# lan8742_daughterboard_EF.net
KiCad netlist of a schematic drawn in Altium Designer
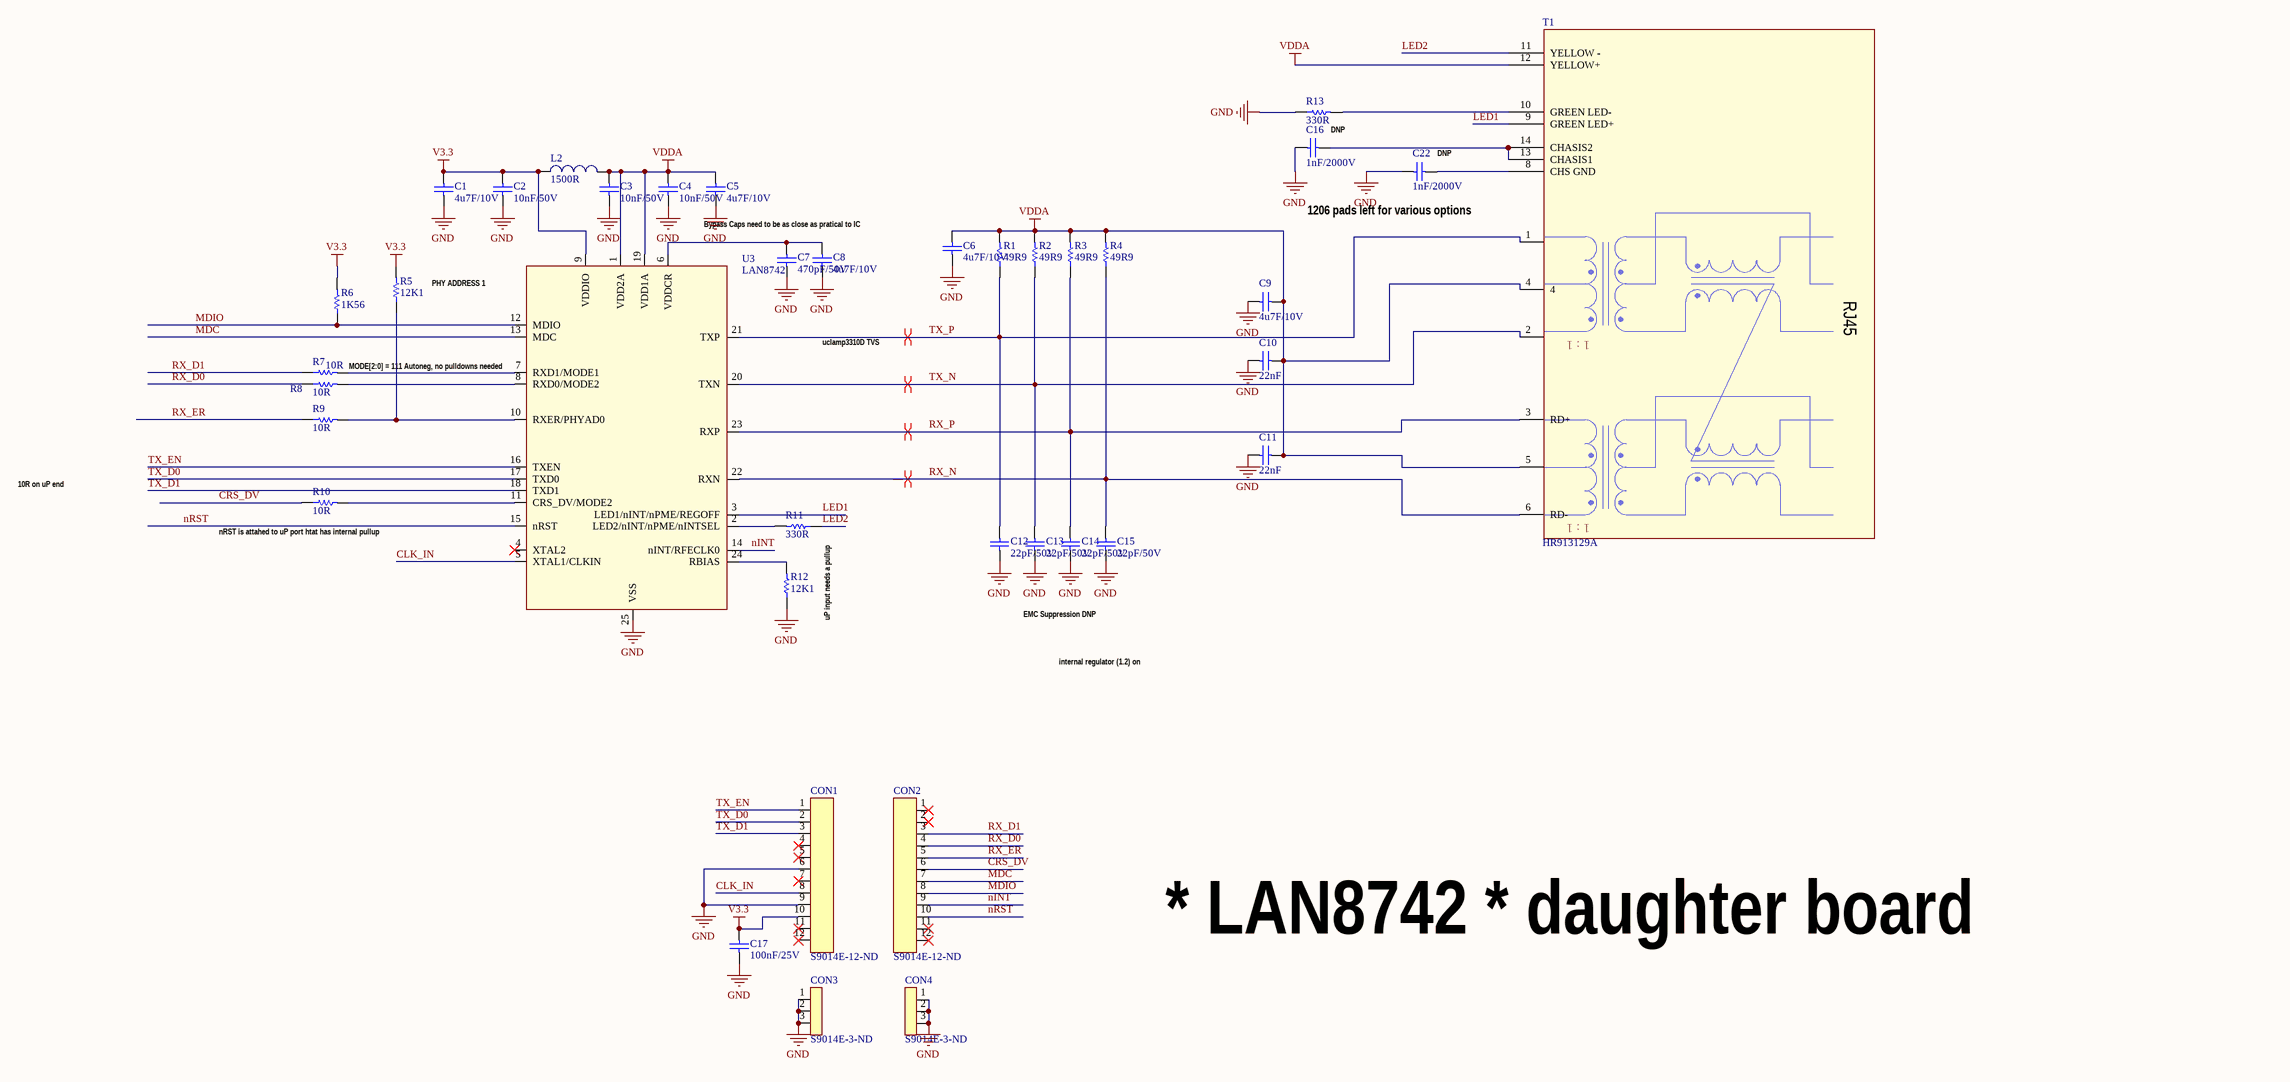
[diagram p0: lan8742_daughterboard_EF.SchDoc]

(export (version "E")
  (design (tool "Eeschema 10.0.6"))
  (components
    (comp (ref "C1")
      (value "CAP")
      (footprint "CAP_0603")
      (fields (field (name "PART NUMBER") "CAP_4u7F/10V_0603") (field (name "PART_VALUE") "4u7F/10V"))
      (libsource (lib "stellalib") (part "CAP"))
    )
    (comp (ref "C2")
      (value "CAP")
      (footprint "CAP_0603")
      (fields (field (name "PART NUMBER") "CAP_10nF/50V_0603") (field (name "PART_VALUE") "10nF/50V"))
      (libsource (lib "stellalib") (part "CAP"))
    )
    (comp (ref "C3")
      (value "CAP")
      (footprint "CAP_0603")
      (fields (field (name "PART NUMBER") "CAP_10nF/50V_0603") (field (name "PART_VALUE") "10nF/50V"))
      (libsource (lib "stellalib") (part "CAP"))
    )
    (comp (ref "C4")
      (value "CAP")
      (footprint "CAP_0603")
      (fields (field (name "PART NUMBER") "CAP_10nF/50V_0603") (field (name "PART_VALUE") "10nF/50V"))
      (libsource (lib "stellalib") (part "CAP"))
    )
    (comp (ref "C5")
      (value "CAP")
      (footprint "CAP_0603")
      (fields (field (name "PART NUMBER") "CAP_4u7F/10V_0603") (field (name "PART_VALUE") "4u7F/10V"))
      (libsource (lib "stellalib") (part "CAP"))
    )
    (comp (ref "C6")
      (value "CAP")
      (footprint "CAP_0603")
      (fields (field (name "PART NUMBER") "CAP_4u7F/10V_0603") (field (name "PART_VALUE") "4u7F/10V"))
      (libsource (lib "stellalib") (part "CAP"))
    )
    (comp (ref "C7")
      (value "CAP")
      (footprint "CAP_0603")
      (description "470pF Ceramic")
      (fields (field (name "PART NUMBER") "CAP_470pF/50V_0603") (field (name "PART_VALUE") "470pF/50V"))
      (libsource (lib "stellalib") (part "CAP"))
    )
    (comp (ref "C8")
      (value "CAP")
      (footprint "CAP_0603")
      (fields (field (name "PART NUMBER") "CAP_4u7F/10V_0603") (field (name "PART_VALUE") "4u7F/10V"))
      (libsource (lib "stellalib") (part "CAP"))
    )
    (comp (ref "C9")
      (value "CAP")
      (footprint "CAP_0603")
      (fields (field (name "PART NUMBER") "CAP_4u7F/10V_0603") (field (name "PART_VALUE") "4u7F/10V"))
      (libsource (lib "stellalib") (part "CAP"))
    )
    (comp (ref "C10")
      (value "CAP")
      (footprint "CAP_0603")
      (fields (field (name "PART NUMBER") "CAP_22nF/50V_0603") (field (name "PART_VALUE") "22nF"))
      (libsource (lib "stellalib") (part "CAP"))
    )
    (comp (ref "C11")
      (value "CAP")
      (footprint "CAP_0603")
      (fields (field (name "PART NUMBER") "CAP_22nF/50V_0603") (field (name "PART_VALUE") "22nF"))
      (libsource (lib "stellalib") (part "CAP"))
    )
    (comp (ref "C12")
      (value "CAP")
      (footprint "CAP_0603")
      (fields (field (name "PART NUMBER") "CAP_22pF/50V_0603") (field (name "PART_VALUE") "22pF/50V"))
      (libsource (lib "stellalib") (part "CAP"))
    )
    (comp (ref "C13")
      (value "CAP")
      (footprint "CAP_0603")
      (fields (field (name "PART NUMBER") "CAP_22pF/50V_0603") (field (name "PART_VALUE") "22pF/50V"))
      (libsource (lib "stellalib") (part "CAP"))
    )
    (comp (ref "C14")
      (value "CAP")
      (footprint "CAP_0603")
      (fields (field (name "PART NUMBER") "CAP_22pF/50V_0603") (field (name "PART_VALUE") "22pF/50V"))
      (libsource (lib "stellalib") (part "CAP"))
    )
    (comp (ref "C15")
      (value "CAP")
      (footprint "CAP_0603")
      (fields (field (name "PART NUMBER") "CAP_22pF/50V_0603") (field (name "PART_VALUE") "22pF/50V"))
      (libsource (lib "stellalib") (part "CAP"))
    )
    (comp (ref "C16")
      (value "CAP")
      (footprint "CAP_1206")
      (fields (field (name "PART NUMBER") "CAP_1nF/2000V_1206") (field (name "PART_VALUE") "1nF/2000V"))
      (libsource (lib "stellalib") (part "CAP"))
    )
    (comp (ref "C17")
      (value "CAP")
      (footprint "CAP_0603")
      (fields (field (name "PART NUMBER") "CAP_100nF/25V_0603") (field (name "PART_VALUE") "100nF/25V"))
      (libsource (lib "stellalib") (part "CAP"))
    )
    (comp (ref "C22")
      (value "CAP")
      (footprint "CAP_1206")
      (fields (field (name "PART NUMBER") "CAP_1nF/2000V_1206") (field (name "PART_VALUE") "1nF/2000V"))
      (libsource (lib "stellalib") (part "CAP"))
    )
    (comp (ref "CON1")
      (value "S9014E-12-ND")
      (footprint "S9014E-12-ND")
      (description "12 way .05\" header plug")
      (libsource (lib "") (part "S9014E-12-ND_1"))
    )
    (comp (ref "CON2")
      (value "S9014E-12-ND")
      (footprint "S9014E-12-ND")
      (description "12 way .05\" header plug")
      (libsource (lib "stellalib") (part "S9014E-12-ND"))
    )
    (comp (ref "CON3")
      (value "S9014E-3-ND")
      (footprint "S9014E-3-ND")
      (description "3 way .05\" header")
      (libsource (lib "") (part "S9014E-3-ND_1"))
    )
    (comp (ref "CON4")
      (value "S9014E-3-ND")
      (footprint "S9014E-3-ND")
      (description "3 way .05\" header")
      (libsource (lib "stellalib") (part "S9014E-3-ND"))
    )
    (comp (ref "L2")
      (value "INDUCTOR")
      (footprint "SMD-0805")
      (description "SMD EMI Suppression Ferrite Bead WE-CBF, Z = 1500 Ohm")
      (fields (field (name "PART NUMBER") "FER_1500R") (field (name "PART_VALUE") "1500R"))
      (libsource (lib "stellalib") (part "INDUCTOR"))
    )
    (comp (ref "R1")
      (value "RES")
      (footprint "RES_0603")
      (description "49R9 .1W 1% SMD")
      (fields (field (name "PART NUMBER") "RES_49R9_0603") (field (name "PART_VALUE") "49R9"))
      (libsource (lib "stellalib") (part "RES"))
    )
    (comp (ref "R2")
      (value "RES")
      (footprint "RES_0603")
      (description "49R9 .1W 1% SMD")
      (fields (field (name "PART NUMBER") "RES_49R9_0603") (field (name "PART_VALUE") "49R9"))
      (libsource (lib "stellalib") (part "RES"))
    )
    (comp (ref "R3")
      (value "RES")
      (footprint "RES_0603")
      (description "49R9 .1W 1% SMD")
      (fields (field (name "PART NUMBER") "RES_49R9_0603") (field (name "PART_VALUE") "49R9"))
      (libsource (lib "stellalib") (part "RES"))
    )
    (comp (ref "R4")
      (value "RES")
      (footprint "RES_0603")
      (description "49R9 .1W 1% SMD")
      (fields (field (name "PART NUMBER") "RES_49R9_0603") (field (name "PART_VALUE") "49R9"))
      (libsource (lib "stellalib") (part "RES"))
    )
    (comp (ref "R5")
      (value "RES")
      (footprint "RES_0603")
      (description "12k1 .1W 1% SMD")
      (fields (field (name "PART NUMBER") "RES_12K1_0603") (field (name "PART_VALUE") "12K1"))
      (libsource (lib "stellalib") (part "RES"))
    )
    (comp (ref "R6")
      (value "RES")
      (footprint "RES_0603")
      (description "1K58 .1W 1% SMD")
      (fields (field (name "PART NUMBER") "RES_1K56_0603") (field (name "PART_VALUE") "1K56"))
      (libsource (lib "stellalib") (part "RES"))
    )
    (comp (ref "R7")
      (value "RES")
      (footprint "RES_0603")
      (fields (field (name "PART NUMBER") "RES_10R_0603") (field (name "PART_VALUE") "10R"))
      (libsource (lib "stellalib") (part "RES"))
    )
    (comp (ref "R8")
      (value "RES")
      (footprint "RES_0603")
      (fields (field (name "PART NUMBER") "RES_10R_0603") (field (name "PART_VALUE") "10R"))
      (libsource (lib "stellalib") (part "RES"))
    )
    (comp (ref "R9")
      (value "RES")
      (footprint "RES_0603")
      (fields (field (name "PART NUMBER") "RES_10R_0603") (field (name "PART_VALUE") "10R"))
      (libsource (lib "stellalib") (part "RES"))
    )
    (comp (ref "R10")
      (value "RES")
      (footprint "RES_0603")
      (fields (field (name "PART NUMBER") "RES_10R_0603") (field (name "PART_VALUE") "10R"))
      (libsource (lib "stellalib") (part "RES"))
    )
    (comp (ref "R11")
      (value "RES")
      (footprint "RES_0603")
      (fields (field (name "PART NUMBER") "RES_330R_0603") (field (name "PART_VALUE") "330R"))
      (libsource (lib "stellalib") (part "RES"))
    )
    (comp (ref "R12")
      (value "RES")
      (footprint "RES_0603")
      (description "12k1 .1W 1% SMD")
      (fields (field (name "PART NUMBER") "RES_12K1_0603") (field (name "PART_VALUE") "12K1"))
      (libsource (lib "stellalib") (part "RES"))
    )
    (comp (ref "R13")
      (value "RES")
      (footprint "RES_0603")
      (fields (field (name "PART NUMBER") "RES_330R_0603") (field (name "PART_VALUE") "330R"))
      (libsource (lib "stellalib") (part "RES"))
    )
    (comp (ref "T1")
      (value "HR913129A")
      (footprint "HR913129A")
      (libsource (lib "stellalib") (part "HR913129A"))
    )
    (comp (ref "U3")
      (value "LAN8742")
      (footprint "LAN8742")
      (description "Lan8742 RMMI PHY")
      (libsource (lib "stellalib") (part "LAN8742"))
    )
  )
  (nets
    (net (code "1") (name "/CLK_IN") (class "Default")
      (node (ref "CON1") (pin "8") (pinfunction "8_8") (pintype "power_in"))
      (node (ref "U3") (pin "5") (pinfunction "XTAL1/CLKIN_5") (pintype "power_in"))
    )
    (net (code "2") (name "/CRS_DV") (class "Default")
      (node (ref "CON2") (pin "6") (pinfunction "6_6") (pintype "power_in"))
      (node (ref "R10") (pin "1") (pinfunction "1_1") (pintype "passive"))
    )
    (net (code "3") (name "/LED1") (class "Default")
      (node (ref "T1") (pin "9") (pinfunction "GREEN_LED+_9") (pintype "passive"))
      (node (ref "U3") (pin "3") (pinfunction "LED1/nINT/nPME/REGOFF_3") (pintype "passive"))
    )
    (net (code "4") (name "/LED2") (class "Default")
      (node (ref "R11") (pin "1") (pinfunction "1_1") (pintype "passive"))
      (node (ref "T1") (pin "11") (pinfunction "YELLOW_-_11") (pintype "passive"))
    )
    (net (code "5") (name "/MDC") (class "Default")
      (node (ref "CON2") (pin "7") (pinfunction "7_7") (pintype "power_in"))
      (node (ref "U3") (pin "13") (pinfunction "MDC_13") (pintype "power_in"))
    )
    (net (code "6") (name "/MDIO") (class "Default")
      (node (ref "CON2") (pin "8") (pinfunction "8_8") (pintype "power_in"))
      (node (ref "R6") (pin "1") (pinfunction "1_1") (pintype "passive"))
      (node (ref "U3") (pin "12") (pinfunction "MDIO_12") (pintype "power_in"))
    )
    (net (code "7") (name "/RX_D0") (class "Default")
      (node (ref "CON2") (pin "4") (pinfunction "4_4") (pintype "power_in"))
      (node (ref "R8") (pin "1") (pinfunction "1_1") (pintype "passive"))
    )
    (net (code "8") (name "/RX_D1") (class "Default")
      (node (ref "CON2") (pin "3") (pinfunction "3_3") (pintype "power_in"))
      (node (ref "R7") (pin "1") (pinfunction "1_1") (pintype "passive"))
    )
    (net (code "9") (name "/RX_ER") (class "Default")
      (node (ref "CON2") (pin "5") (pinfunction "5_5") (pintype "power_in"))
      (node (ref "R9") (pin "1") (pinfunction "1_1") (pintype "passive"))
    )
    (net (code "10") (name "/RX_N") (class "Default")
      (node (ref "C15") (pin "2") (pinfunction "2_2") (pintype "passive"))
      (node (ref "R4") (pin "1") (pinfunction "1_1") (pintype "passive"))
      (node (ref "T1") (pin "6") (pinfunction "RD-_6") (pintype "passive"))
      (node (ref "U3") (pin "22") (pinfunction "RXN_22") (pintype "power_in"))
    )
    (net (code "11") (name "/RX_P") (class "Default")
      (node (ref "C14") (pin "2") (pinfunction "2_2") (pintype "passive"))
      (node (ref "R3") (pin "1") (pinfunction "1_1") (pintype "passive"))
      (node (ref "T1") (pin "3") (pinfunction "RD+_3") (pintype "passive"))
      (node (ref "U3") (pin "23") (pinfunction "RXP_23") (pintype "power_in"))
    )
    (net (code "12") (name "/TX_D0") (class "Default")
      (node (ref "CON1") (pin "2") (pinfunction "2_2") (pintype "power_in"))
      (node (ref "U3") (pin "17") (pinfunction "TXD0_17") (pintype "power_in"))
    )
    (net (code "13") (name "/TX_D1") (class "Default")
      (node (ref "CON1") (pin "3") (pinfunction "3_3") (pintype "power_in"))
      (node (ref "U3") (pin "18") (pinfunction "TXD1_18") (pintype "power_in"))
    )
    (net (code "14") (name "/TX_EN") (class "Default")
      (node (ref "CON1") (pin "1") (pinfunction "1_1") (pintype "power_in"))
      (node (ref "U3") (pin "16") (pinfunction "TXEN_16") (pintype "power_in"))
    )
    (net (code "15") (name "/TX_N") (class "Default")
      (node (ref "C13") (pin "2") (pinfunction "2_2") (pintype "passive"))
      (node (ref "R2") (pin "1") (pinfunction "1_1") (pintype "passive"))
      (node (ref "T1") (pin "2") (pinfunction "TD-_2") (pintype "passive"))
      (node (ref "U3") (pin "20") (pinfunction "TXN_20") (pintype "power_in"))
    )
    (net (code "16") (name "/TX_P") (class "Default")
      (node (ref "C12") (pin "2") (pinfunction "2_2") (pintype "passive"))
      (node (ref "R1") (pin "1") (pinfunction "1_1") (pintype "passive"))
      (node (ref "T1") (pin "1") (pinfunction "TD+_1") (pintype "passive"))
      (node (ref "U3") (pin "21") (pinfunction "TXP_21") (pintype "power_in"))
    )
    (net (code "17") (name "/nINT") (class "Default")
      (node (ref "CON2") (pin "9") (pinfunction "9_9") (pintype "power_in"))
      (node (ref "U3") (pin "14") (pinfunction "nINT/RFECLK0_14") (pintype "power_in"))
    )
    (net (code "18") (name "/nRST") (class "Default")
      (node (ref "CON2") (pin "10") (pinfunction "10_10") (pintype "power_in"))
      (node (ref "U3") (pin "15") (pinfunction "nRST_15") (pintype "power_in"))
    )
    (net (code "19") (name "GND") (class "Default")
      (node (ref "C1") (pin "1") (pinfunction "1_1") (pintype "passive"))
      (node (ref "C10") (pin "2") (pinfunction "2_2") (pintype "passive"))
      (node (ref "C11") (pin "2") (pinfunction "2_2") (pintype "passive"))
      (node (ref "C12") (pin "1") (pinfunction "1_1") (pintype "passive"))
      (node (ref "C13") (pin "1") (pinfunction "1_1") (pintype "passive"))
      (node (ref "C14") (pin "1") (pinfunction "1_1") (pintype "passive"))
      (node (ref "C15") (pin "1") (pinfunction "1_1") (pintype "passive"))
      (node (ref "C16") (pin "1") (pinfunction "1_1") (pintype "passive"))
      (node (ref "C17") (pin "1") (pinfunction "1_1") (pintype "passive"))
      (node (ref "C2") (pin "1") (pinfunction "1_1") (pintype "passive"))
      (node (ref "C22") (pin "1") (pinfunction "1_1") (pintype "passive"))
      (node (ref "C3") (pin "1") (pinfunction "1_1") (pintype "passive"))
      (node (ref "C4") (pin "1") (pinfunction "1_1") (pintype "passive"))
      (node (ref "C5") (pin "1") (pinfunction "1_1") (pintype "passive"))
      (node (ref "C6") (pin "1") (pinfunction "1_1") (pintype "passive"))
      (node (ref "C7") (pin "1") (pinfunction "1_1") (pintype "passive"))
      (node (ref "C8") (pin "1") (pinfunction "1_1") (pintype "passive"))
      (node (ref "C9") (pin "1") (pinfunction "1_1") (pintype "passive"))
      (node (ref "CON1") (pin "6") (pinfunction "6_6") (pintype "power_in"))
      (node (ref "CON1") (pin "9") (pinfunction "9_9") (pintype "power_in"))
      (node (ref "CON3") (pin "1") (pinfunction "1_1") (pintype "power_in"))
      (node (ref "CON3") (pin "2") (pinfunction "2_2") (pintype "power_in"))
      (node (ref "CON3") (pin "3") (pinfunction "3_3") (pintype "power_in"))
      (node (ref "CON4") (pin "1") (pinfunction "1_1") (pintype "power_in"))
      (node (ref "CON4") (pin "2") (pinfunction "2_2") (pintype "power_in"))
      (node (ref "CON4") (pin "3") (pinfunction "3_3") (pintype "power_in"))
      (node (ref "R12") (pin "1") (pinfunction "1_1") (pintype "passive"))
      (node (ref "R13") (pin "1") (pinfunction "1_1") (pintype "passive"))
      (node (ref "U3") (pin "25") (pinfunction "VSS_25") (pintype "power_in"))
    )
    (net (code "20") (name "Net-(T1-CHASIS1)") (class "Default")
      (node (ref "C16") (pin "2") (pinfunction "2_2") (pintype "passive"))
      (node (ref "T1") (pin "13") (pinfunction "CHASIS1_13") (pintype "passive"))
      (node (ref "T1") (pin "14") (pinfunction "CHASIS2_14") (pintype "passive"))
    )
    (net (code "21") (name "Net-(T1-CHS_GND)") (class "Default")
      (node (ref "C22") (pin "2") (pinfunction "2_2") (pintype "passive"))
      (node (ref "T1") (pin "8") (pinfunction "CHS_GND_8") (pintype "passive"))
    )
    (net (code "22") (name "Net-(T1-GREEN_LED-)") (class "Default")
      (node (ref "R13") (pin "2") (pinfunction "2_2") (pintype "passive"))
      (node (ref "T1") (pin "10") (pinfunction "GREEN_LED-_10") (pintype "passive"))
    )
    (net (code "23") (name "Net-(U3-CRS_DV{slash}MODE2)") (class "Default")
      (node (ref "R10") (pin "2") (pinfunction "2_2") (pintype "passive"))
      (node (ref "U3") (pin "11") (pinfunction "CRS_DV/MODE2_11") (pintype "power_in"))
    )
    (net (code "24") (name "Net-(U3-LED2{slash}nINT{slash}nPME{slash}nINTSEL)") (class "Default")
      (node (ref "R11") (pin "2") (pinfunction "2_2") (pintype "passive"))
      (node (ref "U3") (pin "2") (pinfunction "LED2/nINT/nPME/nINTSEL_2") (pintype "passive"))
    )
    (net (code "25") (name "Net-(U3-RBIAS)") (class "Default")
      (node (ref "R12") (pin "2") (pinfunction "2_2") (pintype "passive"))
      (node (ref "U3") (pin "24") (pinfunction "RBIAS_24") (pintype "power_in"))
    )
    (net (code "26") (name "Net-(U3-RXD0{slash}MODE2)") (class "Default")
      (node (ref "R8") (pin "2") (pinfunction "2_2") (pintype "passive"))
      (node (ref "U3") (pin "8") (pinfunction "RXD0/MODE2_8") (pintype "power_in"))
    )
    (net (code "27") (name "Net-(U3-RXD1{slash}MODE1)") (class "Default")
      (node (ref "R7") (pin "2") (pinfunction "2_2") (pintype "passive"))
      (node (ref "U3") (pin "7") (pinfunction "RXD1/MODE1_7") (pintype "power_in"))
    )
    (net (code "28") (name "Net-(U3-RXER{slash}PHYAD0)") (class "Default")
      (node (ref "R5") (pin "1") (pinfunction "1_1") (pintype "passive"))
      (node (ref "R9") (pin "2") (pinfunction "2_2") (pintype "passive"))
      (node (ref "U3") (pin "10") (pinfunction "RXER/PHYAD0_10") (pintype "power_in"))
    )
    (net (code "29") (name "Net-(U3-VDDCR)") (class "Default")
      (node (ref "C7") (pin "2") (pinfunction "2_2") (pintype "passive"))
      (node (ref "C8") (pin "2") (pinfunction "2_2") (pintype "passive"))
      (node (ref "U3") (pin "6") (pinfunction "VDDCR_6") (pintype "power_in"))
    )
    (net (code "30") (name "V3.3") (class "Default")
      (node (ref "C1") (pin "2") (pinfunction "2_2") (pintype "passive"))
      (node (ref "C17") (pin "2") (pinfunction "2_2") (pintype "passive"))
      (node (ref "C2") (pin "2") (pinfunction "2_2") (pintype "passive"))
      (node (ref "CON1") (pin "10") (pinfunction "10_10") (pintype "power_in"))
      (node (ref "L2") (pin "1") (pinfunction "1_1") (pintype "passive"))
      (node (ref "R5") (pin "2") (pinfunction "2_2") (pintype "passive"))
      (node (ref "R6") (pin "2") (pinfunction "2_2") (pintype "passive"))
      (node (ref "U3") (pin "9") (pinfunction "VDDIO_9") (pintype "power_in"))
    )
    (net (code "31") (name "VDDA") (class "Default")
      (node (ref "C10") (pin "1") (pinfunction "1_1") (pintype "passive"))
      (node (ref "C11") (pin "1") (pinfunction "1_1") (pintype "passive"))
      (node (ref "C3") (pin "2") (pinfunction "2_2") (pintype "passive"))
      (node (ref "C4") (pin "2") (pinfunction "2_2") (pintype "passive"))
      (node (ref "C5") (pin "2") (pinfunction "2_2") (pintype "passive"))
      (node (ref "C6") (pin "2") (pinfunction "2_2") (pintype "passive"))
      (node (ref "C9") (pin "2") (pinfunction "2_2") (pintype "passive"))
      (node (ref "L2") (pin "2") (pinfunction "2_2") (pintype "passive"))
      (node (ref "R1") (pin "2") (pinfunction "2_2") (pintype "passive"))
      (node (ref "R2") (pin "2") (pinfunction "2_2") (pintype "passive"))
      (node (ref "R3") (pin "2") (pinfunction "2_2") (pintype "passive"))
      (node (ref "R4") (pin "2") (pinfunction "2_2") (pintype "passive"))
      (node (ref "T1") (pin "12") (pinfunction "YELLOW+_12") (pintype "passive"))
      (node (ref "T1") (pin "4") (pinfunction "4_4") (pintype "passive"))
      (node (ref "T1") (pin "5") (pinfunction "2_5") (pintype "passive"))
      (node (ref "U3") (pin "1") (pinfunction "VDD2A_1") (pintype "power_in"))
      (node (ref "U3") (pin "19") (pinfunction "VDD1A_19") (pintype "power_in"))
    )
    (net (code "32") (name "unconnected-(CON1-Pad4)") (class "Default")
      (node (ref "CON1") (pin "4") (pinfunction "4_4") (pintype "power_in+no_connect"))
    )
    (net (code "33") (name "unconnected-(CON1-Pad5)") (class "Default")
      (node (ref "CON1") (pin "5") (pinfunction "5_5") (pintype "power_in+no_connect"))
    )
    (net (code "34") (name "unconnected-(CON1-Pad7)") (class "Default")
      (node (ref "CON1") (pin "7") (pinfunction "7_7") (pintype "power_in+no_connect"))
    )
    (net (code "35") (name "unconnected-(CON1-Pad11)") (class "Default")
      (node (ref "CON1") (pin "11") (pinfunction "11_11") (pintype "power_in+no_connect"))
    )
    (net (code "36") (name "unconnected-(CON1-Pad12)") (class "Default")
      (node (ref "CON1") (pin "12") (pinfunction "12_12") (pintype "power_in+no_connect"))
    )
    (net (code "37") (name "unconnected-(CON2-Pad1)") (class "Default")
      (node (ref "CON2") (pin "1") (pinfunction "1_1") (pintype "power_in+no_connect"))
    )
    (net (code "38") (name "unconnected-(CON2-Pad2)") (class "Default")
      (node (ref "CON2") (pin "2") (pinfunction "2_2") (pintype "power_in+no_connect"))
    )
    (net (code "39") (name "unconnected-(CON2-Pad11)") (class "Default")
      (node (ref "CON2") (pin "11") (pinfunction "11_11") (pintype "power_in+no_connect"))
    )
    (net (code "40") (name "unconnected-(CON2-Pad12)") (class "Default")
      (node (ref "CON2") (pin "12") (pinfunction "12_12") (pintype "power_in+no_connect"))
    )
    (net (code "41") (name "unconnected-(U3-XTAL2-Pad4)") (class "Default")
      (node (ref "U3") (pin "4") (pinfunction "XTAL2_4") (pintype "passive+no_connect"))
    )
  )
)
